# AD9837_DDS.net
KiCad netlist of a schematic drawn in Altium Designer
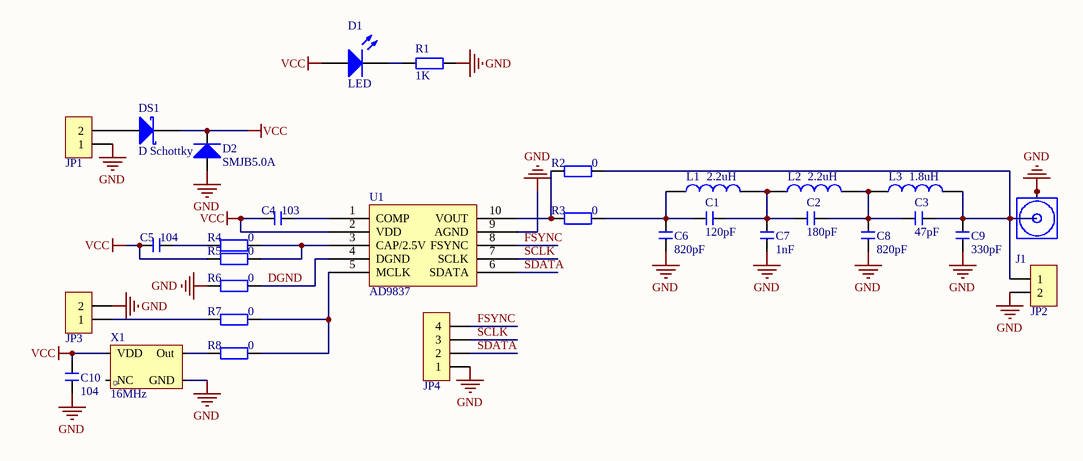
[diagram p0: AD9837_DDS.SchDoc]

(export (version "E")
  (design (tool "Eeschema 10.0.6"))
  (components
    (comp (ref "C1")
      (value "120pF")
      (footprint "C 0603")
      (description "无极性贴片电容")
      (fields (field (name "版权归属") "源创客"))
      (libsource (lib "电阻-电容-电感") (part "C"))
    )
    (comp (ref "C2")
      (value "180pF")
      (footprint "C 0603")
      (description "无极性贴片电容")
      (fields (field (name "版权归属") "源创客"))
      (libsource (lib "电阻-电容-电感") (part "C"))
    )
    (comp (ref "C3")
      (value "47pF")
      (footprint "C 0603")
      (description "无极性贴片电容")
      (fields (field (name "版权归属") "源创客"))
      (libsource (lib "电阻-电容-电感") (part "C"))
    )
    (comp (ref "C4")
      (value "103")
      (footprint "C 0603")
      (description "无极性贴片电容")
      (fields (field (name "版权归属") "源创客"))
      (libsource (lib "电阻-电容-电感") (part "C"))
    )
    (comp (ref "C5")
      (value "104")
      (footprint "C 0603")
      (description "无极性贴片电容")
      (fields (field (name "版权归属") "源创客"))
      (libsource (lib "电阻-电容-电感") (part "C"))
    )
    (comp (ref "C6")
      (value "820pF")
      (footprint "C 0603")
      (description "无极性贴片电容")
      (fields (field (name "版权归属") "源创客"))
      (libsource (lib "电阻-电容-电感") (part "C"))
    )
    (comp (ref "C7")
      (value "1nF")
      (footprint "C 0603")
      (description "无极性贴片电容")
      (fields (field (name "版权归属") "源创客"))
      (libsource (lib "电阻-电容-电感") (part "C"))
    )
    (comp (ref "C8")
      (value "820pF")
      (footprint "C 0603")
      (description "无极性贴片电容")
      (fields (field (name "版权归属") "源创客"))
      (libsource (lib "电阻-电容-电感") (part "C"))
    )
    (comp (ref "C9")
      (value "330pF")
      (footprint "C 0603")
      (description "无极性贴片电容")
      (fields (field (name "版权归属") "源创客"))
      (libsource (lib "电阻-电容-电感") (part "C"))
    )
    (comp (ref "C10")
      (value "104")
      (footprint "C 0603")
      (description "无极性贴片电容")
      (fields (field (name "版权归属") "源创客"))
      (libsource (lib "电阻-电容-电感") (part "C"))
    )
    (comp (ref "D1")
      (value "LED")
      (footprint "0603")
      (description "发光二极管")
      (fields (field (name "PUBLISHER") "Altium Limited"))
      (libsource (lib "LIB") (part "LED"))
    )
    (comp (ref "D2")
      (value "TVS")
      (footprint "DIODE-SMA")
      (description "TVS保护")
      (fields (field (name "TYPE") "SMJB5.0A") (field (name "PUBLISHER") "Altium Limited"))
      (libsource (lib "LIB") (part "TVS"))
    )
    (comp (ref "DS1")
      (value "D Schottky")
      (footprint "DIODE-SMA")
      (description "Schottky Diode")
      (fields (field (name "PUBLISHER") "Altium Limited"))
      (libsource (lib "LIB") (part "D Schottky"))
    )
    (comp (ref "J1") (value "COAX") (footprint "MCX5.08-5-H") (libsource (lib "LIB") (part "COAX")))
    (comp (ref "JP1")
      (value "HDR-1X2")
      (footprint "XH2.54-2P_H")
      (description "2P接插件")
      (fields (field (name "版权归属") "源创客"))
      (libsource (lib "接插件") (part "Header 2"))
    )
    (comp (ref "JP2")
      (value "HDR-1X2")
      (footprint "HDR-1X2")
      (description "2P接插件")
      (fields (field (name "版权归属") "源创客"))
      (libsource (lib "") (part "Header 2_1"))
    )
    (comp (ref "JP3")
      (value "HDR-1X2")
      (footprint "HDR-1X2")
      (description "2P接插件")
      (fields (field (name "版权归属") "源创客"))
      (libsource (lib "接插件") (part "Header 2"))
    )
    (comp (ref "JP4")
      (value "HDR-1X4")
      (footprint "HDR-1X4")
      (description "4P接插件")
      (fields (field (name "版权归属") "源创客"))
      (libsource (lib "接插件") (part "Header 4"))
    )
    (comp (ref "L1")
      (value "2.2uH")
      (footprint "L 0603")
      (description "小功率贴片电感")
      (fields (field (name "版权归属") "源创客"))
      (libsource (lib "电阻-电容-电感") (part "L"))
    )
    (comp (ref "L2")
      (value "2.2uH")
      (footprint "L 0603")
      (description "小功率贴片电感")
      (fields (field (name "版权归属") "源创客"))
      (libsource (lib "电阻-电容-电感") (part "L"))
    )
    (comp (ref "L3")
      (value "1.8uH")
      (footprint "L 0603")
      (description "小功率贴片电感")
      (fields (field (name "版权归属") "源创客"))
      (libsource (lib "电阻-电容-电感") (part "L"))
    )
    (comp (ref "R1")
      (value "1K")
      (footprint "R 0603")
      (description "贴片电阻")
      (fields (field (name "版权归属") "源创客"))
      (libsource (lib "电阻-电容-电感") (part "R"))
    )
    (comp (ref "R2")
      (value "0")
      (footprint "R 0603")
      (description "贴片电阻")
      (fields (field (name "版权归属") "源创客"))
      (libsource (lib "电阻-电容-电感") (part "R"))
    )
    (comp (ref "R3")
      (value "0")
      (footprint "R 0603")
      (description "贴片电阻")
      (fields (field (name "版权归属") "源创客"))
      (libsource (lib "电阻-电容-电感") (part "R"))
    )
    (comp (ref "R4")
      (value "0")
      (footprint "R 0603")
      (description "贴片电阻")
      (fields (field (name "版权归属") "源创客"))
      (libsource (lib "电阻-电容-电感") (part "R"))
    )
    (comp (ref "R5")
      (value "0")
      (footprint "R 0603")
      (description "贴片电阻")
      (fields (field (name "版权归属") "源创客"))
      (libsource (lib "电阻-电容-电感") (part "R"))
    )
    (comp (ref "R6")
      (value "0")
      (footprint "R 0603")
      (description "贴片电阻")
      (fields (field (name "版权归属") "源创客"))
      (libsource (lib "电阻-电容-电感") (part "R"))
    )
    (comp (ref "R7")
      (value "0")
      (footprint "R 0603")
      (description "贴片电阻")
      (fields (field (name "版权归属") "源创客"))
      (libsource (lib "电阻-电容-电感") (part "R"))
    )
    (comp (ref "R8")
      (value "0")
      (footprint "R 0603")
      (description "贴片电阻")
      (fields (field (name "版权归属") "源创客"))
      (libsource (lib "电阻-电容-电感") (part "R"))
    )
    (comp (ref "U1")
      (value "AD9837")
      (footprint "CP-10-9")
      (description "低功耗、8.5mW、2.3V至5.5V可编程波形发生器")
      (libsource (lib "LIB") (part "AD9837"))
    )
    (comp (ref "X1")
      (value "XTAL")
      (footprint "XTAL-3225")
      (description "有源晶振")
      (fields (field (name "FREQUENCY") "16MHz"))
      (libsource (lib "LIB") (part "XTAL_Oscillator"))
    )
  )
  (nets
    (net (code "1") (name "/DGND") (class "Default")
      (node (ref "R6") (pin "2") (pinfunction "2_2") (pintype "passive"))
      (node (ref "U1") (pin "4") (pinfunction "DGND_4") (pintype "passive"))
    )
    (net (code "2") (name "/FSYNC") (class "Default")
      (node (ref "JP4") (pin "4") (pinfunction "4_4") (pintype "passive"))
      (node (ref "U1") (pin "8") (pinfunction "FSYNC_8") (pintype "passive"))
    )
    (net (code "3") (name "/SCLK") (class "Default")
      (node (ref "JP4") (pin "3") (pinfunction "3_3") (pintype "passive"))
      (node (ref "U1") (pin "7") (pinfunction "SCLK_7") (pintype "passive"))
    )
    (net (code "4") (name "/SDATA") (class "Default")
      (node (ref "JP4") (pin "2") (pinfunction "2_2") (pintype "passive"))
      (node (ref "U1") (pin "6") (pinfunction "SDATA_6") (pintype "passive"))
    )
    (net (code "5") (name "GND") (class "Default")
      (node (ref "C10") (pin "1") (pinfunction "1_1") (pintype "passive"))
      (node (ref "C6") (pin "1") (pinfunction "1_1") (pintype "passive"))
      (node (ref "C7") (pin "2") (pinfunction "2_2") (pintype "passive"))
      (node (ref "C8") (pin "1") (pinfunction "1_1") (pintype "passive"))
      (node (ref "C9") (pin "2") (pinfunction "2_2") (pintype "passive"))
      (node (ref "D2") (pin "1") (pinfunction "A_1") (pintype "passive"))
      (node (ref "J1") (pin "2") (pinfunction "GND_2") (pintype "passive"))
      (node (ref "J1") (pin "3") (pinfunction "GND_3") (pintype "passive"))
      (node (ref "J1") (pin "4") (pinfunction "GND_4") (pintype "passive"))
      (node (ref "J1") (pin "5") (pinfunction "GND_5") (pintype "passive"))
      (node (ref "JP1") (pin "1") (pinfunction "1_1") (pintype "passive"))
      (node (ref "JP2") (pin "2") (pinfunction "2_2") (pintype "passive"))
      (node (ref "JP3") (pin "2") (pinfunction "2_2") (pintype "passive"))
      (node (ref "JP4") (pin "1") (pinfunction "1_1") (pintype "passive"))
      (node (ref "R1") (pin "2") (pinfunction "2_2") (pintype "passive"))
      (node (ref "R6") (pin "1") (pinfunction "1_1") (pintype "passive"))
      (node (ref "U1") (pin "9") (pinfunction "AGND_9") (pintype "passive"))
      (node (ref "X1") (pin "2") (pinfunction "GND_2") (pintype "passive"))
    )
    (net (code "6") (name "Net-(C1-Pad1)") (class "Default")
      (node (ref "C1") (pin "1") (pinfunction "1_1") (pintype "passive"))
      (node (ref "C2") (pin "1") (pinfunction "1_1") (pintype "passive"))
      (node (ref "C7") (pin "1") (pinfunction "1_1") (pintype "passive"))
      (node (ref "L1") (pin "2") (pinfunction "2_2") (pintype "passive"))
      (node (ref "L2") (pin "1") (pinfunction "1_1") (pintype "passive"))
    )
    (net (code "7") (name "Net-(C1-Pad2)") (class "Default")
      (node (ref "C1") (pin "2") (pinfunction "2_2") (pintype "passive"))
      (node (ref "C6") (pin "2") (pinfunction "2_2") (pintype "passive"))
      (node (ref "L1") (pin "1") (pinfunction "1_1") (pintype "passive"))
      (node (ref "R3") (pin "2") (pinfunction "2_2") (pintype "passive"))
    )
    (net (code "8") (name "Net-(C2-Pad2)") (class "Default")
      (node (ref "C2") (pin "2") (pinfunction "2_2") (pintype "passive"))
      (node (ref "C3") (pin "2") (pinfunction "2_2") (pintype "passive"))
      (node (ref "C8") (pin "2") (pinfunction "2_2") (pintype "passive"))
      (node (ref "L2") (pin "2") (pinfunction "2_2") (pintype "passive"))
      (node (ref "L3") (pin "1") (pinfunction "1_1") (pintype "passive"))
    )
    (net (code "9") (name "Net-(C5-Pad2)") (class "Default")
      (node (ref "C5") (pin "2") (pinfunction "2_2") (pintype "passive"))
      (node (ref "R4") (pin "1") (pinfunction "1_1") (pintype "passive"))
    )
    (net (code "10") (name "Net-(D1-K)") (class "Default")
      (node (ref "D1") (pin "2") (pinfunction "K_2") (pintype "passive"))
      (node (ref "R1") (pin "1") (pinfunction "1_1") (pintype "passive"))
    )
    (net (code "11") (name "Net-(DS1-Pad1)") (class "Default")
      (node (ref "DS1") (pin "1") (pinfunction "1_1") (pintype "passive"))
      (node (ref "JP1") (pin "2") (pinfunction "2_2") (pintype "passive"))
    )
    (net (code "12") (name "Net-(J1-Signal)") (class "Default")
      (node (ref "C3") (pin "1") (pinfunction "1_1") (pintype "passive"))
      (node (ref "C9") (pin "1") (pinfunction "1_1") (pintype "passive"))
      (node (ref "J1") (pin "1") (pinfunction "Signal_1") (pintype "passive"))
      (node (ref "JP2") (pin "1") (pinfunction "1_1") (pintype "passive"))
      (node (ref "L3") (pin "2") (pinfunction "2_2") (pintype "passive"))
      (node (ref "R2") (pin "2") (pinfunction "2_2") (pintype "passive"))
    )
    (net (code "13") (name "Net-(JP3-Pad1)") (class "Default")
      (node (ref "JP3") (pin "1") (pinfunction "1_1") (pintype "passive"))
      (node (ref "R7") (pin "1") (pinfunction "1_1") (pintype "passive"))
    )
    (net (code "14") (name "Net-(U1-CAP{slash}2.5V)") (class "Default")
      (node (ref "R4") (pin "2") (pinfunction "2_2") (pintype "passive"))
      (node (ref "R5") (pin "2") (pinfunction "2_2") (pintype "passive"))
      (node (ref "U1") (pin "3") (pinfunction "CAP/2.5V_3") (pintype "passive"))
    )
    (net (code "15") (name "Net-(U1-COMP)") (class "Default")
      (node (ref "C4") (pin "1") (pinfunction "1_1") (pintype "passive"))
      (node (ref "U1") (pin "1") (pinfunction "COMP_1") (pintype "passive"))
    )
    (net (code "16") (name "Net-(U1-MCLK)") (class "Default")
      (node (ref "R7") (pin "2") (pinfunction "2_2") (pintype "passive"))
      (node (ref "R8") (pin "2") (pinfunction "2_2") (pintype "passive"))
      (node (ref "U1") (pin "5") (pinfunction "MCLK_5") (pintype "passive"))
    )
    (net (code "17") (name "Net-(U1-VOUT)") (class "Default")
      (node (ref "R2") (pin "1") (pinfunction "1_1") (pintype "passive"))
      (node (ref "R3") (pin "1") (pinfunction "1_1") (pintype "passive"))
      (node (ref "U1") (pin "10") (pinfunction "VOUT_10") (pintype "passive"))
    )
    (net (code "18") (name "Net-(X1-Out)") (class "Default")
      (node (ref "R8") (pin "1") (pinfunction "1_1") (pintype "passive"))
      (node (ref "X1") (pin "3") (pinfunction "Out_3") (pintype "passive"))
    )
    (net (code "19") (name "VCC") (class "Default")
      (node (ref "C10") (pin "2") (pinfunction "2_2") (pintype "passive"))
      (node (ref "C4") (pin "2") (pinfunction "2_2") (pintype "passive"))
      (node (ref "C5") (pin "1") (pinfunction "1_1") (pintype "passive"))
      (node (ref "D1") (pin "1") (pinfunction "A_1") (pintype "passive"))
      (node (ref "D2") (pin "2") (pinfunction "K_2") (pintype "passive"))
      (node (ref "DS1") (pin "2") (pinfunction "2_2") (pintype "passive"))
      (node (ref "R5") (pin "1") (pinfunction "1_1") (pintype "passive"))
      (node (ref "U1") (pin "2") (pinfunction "VDD_2") (pintype "passive"))
      (node (ref "X1") (pin "4") (pinfunction "VDD_4") (pintype "passive"))
    )
    (net (code "20") (name "unconnected-(X1-NC-Pad1)") (class "Default")
      (node (ref "X1") (pin "1") (pinfunction "NC_1") (pintype "passive"))
    )
  )
)
